# ig-normal-ver11.net
KiCad netlist of a schematic drawn in EAGLE
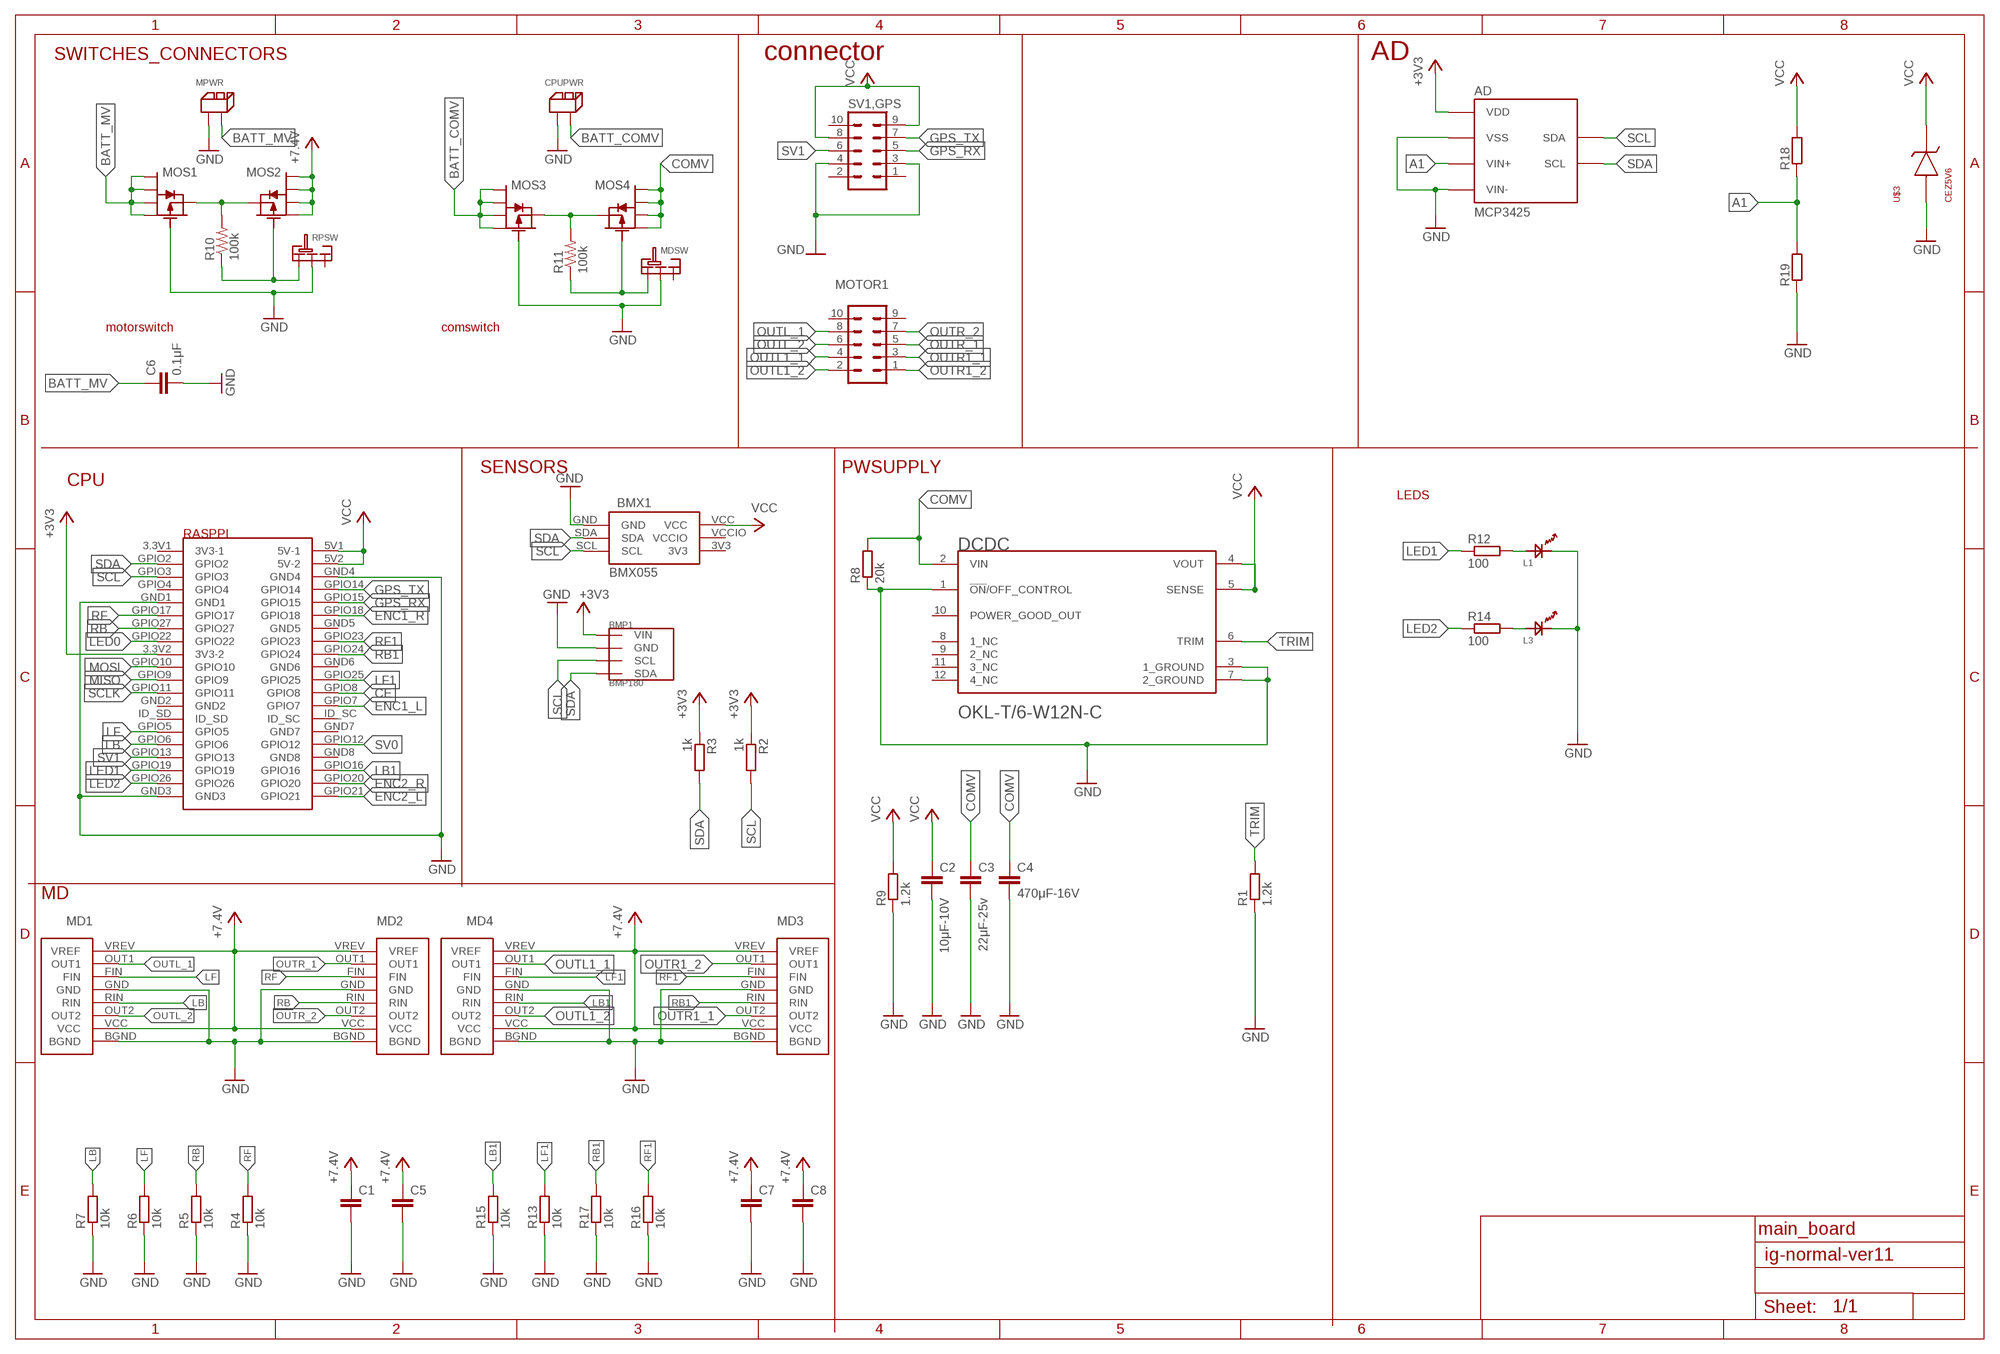
[diagram p0: schematic, sheet 1]

(export (version "E")
  (design (tool "Eeschema 10.0.6"))
  (components
    (comp (ref "AD")
      (value "MCP3425")
      (footprint "eagle-import:SOT23-6")
      (libsource (lib "eagle-import") (part "MCP3425"))
    )
    (comp (ref "BMP1")
      (value "BMP180")
      (footprint "eagle-import:GY-68")
      (libsource (lib "eagle-import") (part "BMP180"))
    )
    (comp (ref "BMX1")
      (value "BMX055")
      (footprint "eagle-import:BMX055")
      (libsource (lib "eagle-import") (part "BMX055"))
    )
    (comp (ref "C1")
      (value "C-EUC0603")
      (footprint "eagle-import:C0603")
      (libsource (lib "eagle-import") (part "C-EUC0603"))
    )
    (comp (ref "C2")
      (value "10μF-10V")
      (footprint "eagle-import:C0603")
      (libsource (lib "eagle-import") (part "C-EUC0603"))
    )
    (comp (ref "C3")
      (value "22μF-25v")
      (footprint "eagle-import:C0805")
      (libsource (lib "eagle-import") (part "C-EUC0805"))
    )
    (comp (ref "C4")
      (value "470μF-16V")
      (footprint "eagle-import:C0603")
      (libsource (lib "eagle-import") (part "C-EUC0603"))
    )
    (comp (ref "C5")
      (value "C-EUC0603")
      (footprint "eagle-import:C0603")
      (libsource (lib "eagle-import") (part "C-EUC0603"))
    )
    (comp (ref "C6")
      (value "0.1μF")
      (footprint "eagle-import:C0603")
      (libsource (lib "eagle-import") (part "C-EUC0603"))
    )
    (comp (ref "C7")
      (value "C-EUC0603")
      (footprint "eagle-import:C0603")
      (libsource (lib "eagle-import") (part "C-EUC0603"))
    )
    (comp (ref "C8")
      (value "C-EUC0603")
      (footprint "eagle-import:C0603")
      (libsource (lib "eagle-import") (part "C-EUC0603"))
    )
    (comp (ref "CPUPWR")
      (value "2PIN")
      (footprint "eagle-import:2PIN")
      (libsource (lib "eagle-import") (part "2PIN"))
    )
    (comp (ref "DCDC")
      (value "OKL-T/6-W12N-CMURATA_OKL-T-6-W12N-C_0_0")
      (footprint "eagle-import:MURATA_OKL-T-6-W12N-C_0")
      (fields
        (field (name "DIGIKEY_PART_NUMBER") "811-2214-1-ND")
        (field (name "MF") "Murata")
        (field (name "MOUSER_PART_NUMBER") "580-OKL-T/6-W12N-C")
      )
      (libsource (lib "eagle-import") (part "OKL-T/6-W12N-CMURATA_OKL-T-6-W12N-C_0_0"))
    )
    (comp (ref "L1")
      (value "OSXX1608C1A")
      (footprint "eagle-import:OSXX1608C1A")
      (libsource (lib "eagle-import") (part "OSXX1608C1A"))
    )
    (comp (ref "L3")
      (value "OSXX1608C1A")
      (footprint "eagle-import:OSXX1608C1A")
      (libsource (lib "eagle-import") (part "OSXX1608C1A"))
    )
    (comp (ref "MD1")
      (value "BD6222HFP-TR")
      (footprint "eagle-import:BD6222HFP-TR")
      (libsource (lib "eagle-import") (part "BD6222HFP-TR"))
    )
    (comp (ref "MD2")
      (value "BD6222HFP-TR")
      (footprint "eagle-import:BD6222HFP-TR")
      (libsource (lib "eagle-import") (part "BD6222HFP-TR"))
    )
    (comp (ref "MD3")
      (value "BD6222HFP-TR")
      (footprint "eagle-import:BD6222HFP-TR")
      (libsource (lib "eagle-import") (part "BD6222HFP-TR"))
    )
    (comp (ref "MD4")
      (value "BD6222HFP-TR")
      (footprint "eagle-import:BD6222HFP-TR")
      (libsource (lib "eagle-import") (part "BD6222HFP-TR"))
    )
    (comp (ref "MDSW")
      (value "SRIDE_SWITCH")
      (footprint "eagle-import:SRIDE_SWITCH")
      (libsource (lib "eagle-import") (part "SRIDE_SWITCH"))
    )
    (comp (ref "MOS1")
      (value "PCH_SSM6J808R")
      (footprint "eagle-import:SSM6J808R")
      (libsource (lib "eagle-import") (part "PCH_SSM6J808R"))
    )
    (comp (ref "MOS2")
      (value "PCH_SSM6J808R")
      (footprint "eagle-import:SSM6J808R")
      (libsource (lib "eagle-import") (part "PCH_SSM6J808R"))
    )
    (comp (ref "MOS3")
      (value "PCH_SSM6J808R")
      (footprint "eagle-import:SSM6J808R")
      (libsource (lib "eagle-import") (part "PCH_SSM6J808R"))
    )
    (comp (ref "MOS4")
      (value "PCH_SSM6J808R")
      (footprint "eagle-import:SSM6J808R")
      (libsource (lib "eagle-import") (part "PCH_SSM6J808R"))
    )
    (comp (ref "MOTOR1")
      (value "ML10L")
      (footprint "eagle-import:ML10L")
      (libsource (lib "eagle-import") (part "ML10L"))
    )
    (comp (ref "MPWR")
      (value "2PIN")
      (footprint "eagle-import:2PIN")
      (libsource (lib "eagle-import") (part "2PIN"))
    )
    (comp (ref "R1")
      (value "1.2k")
      (footprint "eagle-import:R0805")
      (libsource (lib "eagle-import") (part "R-EU_R0805"))
    )
    (comp (ref "R2")
      (value "1k")
      (footprint "eagle-import:R0603")
      (libsource (lib "eagle-import") (part "R-EU_R0603"))
    )
    (comp (ref "R3")
      (value "1k")
      (footprint "eagle-import:R0603")
      (libsource (lib "eagle-import") (part "R-EU_R0603"))
    )
    (comp (ref "R4")
      (value "10k")
      (footprint "eagle-import:R0603")
      (libsource (lib "eagle-import") (part "R-EU_R0603"))
    )
    (comp (ref "R5")
      (value "10k")
      (footprint "eagle-import:R0603")
      (libsource (lib "eagle-import") (part "R-EU_R0603"))
    )
    (comp (ref "R6")
      (value "10k")
      (footprint "eagle-import:R0603")
      (libsource (lib "eagle-import") (part "R-EU_R0603"))
    )
    (comp (ref "R7")
      (value "10k")
      (footprint "eagle-import:R0603")
      (libsource (lib "eagle-import") (part "R-EU_R0603"))
    )
    (comp (ref "R8")
      (value "20k")
      (footprint "eagle-import:R0603")
      (libsource (lib "eagle-import") (part "R-EU_R0603"))
    )
    (comp (ref "R9")
      (value "1.2k")
      (footprint "eagle-import:R0805")
      (libsource (lib "eagle-import") (part "R-EU_R0805"))
    )
    (comp (ref "R10")
      (value "100k")
      (footprint "eagle-import:R0603")
      (libsource (lib "eagle-import") (part "R-US_R0603"))
    )
    (comp (ref "R11")
      (value "100k")
      (footprint "eagle-import:R0603")
      (libsource (lib "eagle-import") (part "R-US_R0603"))
    )
    (comp (ref "R12")
      (value "100")
      (footprint "eagle-import:R0603")
      (libsource (lib "eagle-import") (part "R-EU_R0603"))
    )
    (comp (ref "R13")
      (value "10k")
      (footprint "eagle-import:R0603")
      (libsource (lib "eagle-import") (part "R-EU_R0603"))
    )
    (comp (ref "R14")
      (value "100")
      (footprint "eagle-import:R0603")
      (libsource (lib "eagle-import") (part "R-EU_R0603"))
    )
    (comp (ref "R15")
      (value "10k")
      (footprint "eagle-import:R0603")
      (libsource (lib "eagle-import") (part "R-EU_R0603"))
    )
    (comp (ref "R16")
      (value "10k")
      (footprint "eagle-import:R0603")
      (libsource (lib "eagle-import") (part "R-EU_R0603"))
    )
    (comp (ref "R17")
      (value "10k")
      (footprint "eagle-import:R0603")
      (libsource (lib "eagle-import") (part "R-EU_R0603"))
    )
    (comp (ref "R18")
      (value "R-EU_R0603")
      (footprint "eagle-import:R0603")
      (libsource (lib "eagle-import") (part "R-EU_R0603"))
    )
    (comp (ref "R19")
      (value "R-EU_R0603")
      (footprint "eagle-import:R0603")
      (libsource (lib "eagle-import") (part "R-EU_R0603"))
    )
    (comp (ref "RASPPI")
      (value "RASPBERYPIZEROW")
      (footprint "eagle-import:RASPBERYPIZEROW")
      (libsource (lib "eagle-import") (part "RASPBERYPIZEROW"))
    )
    (comp (ref "RPSW")
      (value "SRIDE_SWITCH")
      (footprint "eagle-import:SRIDE_SWITCH")
      (libsource (lib "eagle-import") (part "SRIDE_SWITCH"))
    )
    (comp (ref "SV1,GPS")
      (value "ML10L")
      (footprint "eagle-import:ML10L")
      (libsource (lib "eagle-import") (part "ML10L"))
    )
    (comp (ref "U$3")
      (value "CEZ5V6")
      (footprint "eagle-import:CEZ5V6")
      (libsource (lib "eagle-import") (part "CEZ5V6"))
    )
  )
  (nets
    (net (code "1") (name "+3V3") (class "Default")
      (node (ref "AD") (pin "5") (pinfunction "VDD_5") (pintype "power_in"))
      (node (ref "BMP1") (pin "P1") (pinfunction "VIN_P1") (pintype "bidirectional"))
      (node (ref "R2") (pin "1") (pinfunction "1_1") (pintype "passive"))
      (node (ref "R3") (pin "1") (pinfunction "1_1") (pintype "passive"))
      (node (ref "RASPPI") (pin "3.3V2") (pinfunction "3V3-2_3.3V2") (pintype "bidirectional"))
    )
    (net (code "2") (name "+7.4V") (class "Default")
      (node (ref "C1") (pin "1") (pinfunction "1_1") (pintype "passive"))
      (node (ref "C5") (pin "1") (pinfunction "1_1") (pintype "passive"))
      (node (ref "C7") (pin "1") (pinfunction "1_1") (pintype "passive"))
      (node (ref "C8") (pin "1") (pinfunction "1_1") (pintype "passive"))
      (node (ref "MD1") (pin "VCC") (pinfunction "VCC_VCC") (pintype "bidirectional"))
      (node (ref "MD1") (pin "VREV") (pinfunction "VREF_VREV") (pintype "bidirectional"))
      (node (ref "MD2") (pin "VCC") (pinfunction "VCC_VCC") (pintype "bidirectional"))
      (node (ref "MD2") (pin "VREV") (pinfunction "VREF_VREV") (pintype "bidirectional"))
      (node (ref "MD3") (pin "VCC") (pinfunction "VCC_VCC") (pintype "bidirectional"))
      (node (ref "MD3") (pin "VREV") (pinfunction "VREF_VREV") (pintype "bidirectional"))
      (node (ref "MD4") (pin "VCC") (pinfunction "VCC_VCC") (pintype "bidirectional"))
      (node (ref "MD4") (pin "VREV") (pinfunction "VREF_VREV") (pintype "bidirectional"))
      (node (ref "MOS2") (pin "1") (pinfunction "1_1") (pintype "bidirectional"))
      (node (ref "MOS2") (pin "2") (pinfunction "2_2") (pintype "bidirectional"))
      (node (ref "MOS2") (pin "5") (pinfunction "5_5") (pintype "bidirectional"))
      (node (ref "MOS2") (pin "6") (pinfunction "6_6") (pintype "bidirectional"))
    )
    (net (code "3") (name "/3V3") (class "Default")
      (node (ref "BMX1") (pin "3V3") (pinfunction "3V3_3V3") (pintype "power_in"))
    )
    (net (code "4") (name "/VCCIO") (class "Default")
      (node (ref "BMX1") (pin "VCCIO") (pinfunction "VCCIO_VCCIO") (pintype "power_in"))
    )
    (net (code "5") (name "A1") (class "Default")
      (node (ref "AD") (pin "1") (pinfunction "VIN+_1") (pintype "input"))
      (node (ref "R18") (pin "1") (pinfunction "1_1") (pintype "passive"))
      (node (ref "R19") (pin "2") (pinfunction "2_2") (pintype "passive"))
    )
    (net (code "6") (name "BATT_COMV") (class "Default")
      (node (ref "CPUPWR") (pin "P$2") (pinfunction "P$2_P$2") (pintype "bidirectional"))
      (node (ref "MOS3") (pin "1") (pinfunction "1_1") (pintype "bidirectional"))
      (node (ref "MOS3") (pin "2") (pinfunction "2_2") (pintype "bidirectional"))
      (node (ref "MOS3") (pin "5") (pinfunction "5_5") (pintype "bidirectional"))
      (node (ref "MOS3") (pin "6") (pinfunction "6_6") (pintype "bidirectional"))
    )
    (net (code "7") (name "BATT_MV") (class "Default")
      (node (ref "C6") (pin "1") (pinfunction "1_1") (pintype "passive"))
      (node (ref "MOS1") (pin "1") (pinfunction "1_1") (pintype "bidirectional"))
      (node (ref "MOS1") (pin "2") (pinfunction "2_2") (pintype "bidirectional"))
      (node (ref "MOS1") (pin "5") (pinfunction "5_5") (pintype "bidirectional"))
      (node (ref "MOS1") (pin "6") (pinfunction "6_6") (pintype "bidirectional"))
      (node (ref "MPWR") (pin "P$2") (pinfunction "P$2_P$2") (pintype "bidirectional"))
    )
    (net (code "8") (name "CE") (class "Default")
      (node (ref "RASPPI") (pin "GPIO8") (pinfunction "GPIO8_GPIO8") (pintype "bidirectional"))
    )
    (net (code "9") (name "COMV") (class "Default")
      (node (ref "C3") (pin "1") (pinfunction "1_1") (pintype "passive"))
      (node (ref "C4") (pin "1") (pinfunction "1_1") (pintype "passive"))
      (node (ref "DCDC") (pin "2") (pinfunction "VIN_2") (pintype "bidirectional"))
      (node (ref "MOS4") (pin "1") (pinfunction "1_1") (pintype "bidirectional"))
      (node (ref "MOS4") (pin "2") (pinfunction "2_2") (pintype "bidirectional"))
      (node (ref "MOS4") (pin "5") (pinfunction "5_5") (pintype "bidirectional"))
      (node (ref "MOS4") (pin "6") (pinfunction "6_6") (pintype "bidirectional"))
      (node (ref "R8") (pin "2") (pinfunction "2_2") (pintype "passive"))
    )
    (net (code "10") (name "ENC1_L") (class "Default")
      (node (ref "RASPPI") (pin "GPIO7") (pinfunction "GPIO7_GPIO7") (pintype "bidirectional"))
    )
    (net (code "11") (name "ENC1_R") (class "Default")
      (node (ref "RASPPI") (pin "GPIO18") (pinfunction "GPIO18_GPIO18") (pintype "bidirectional"))
    )
    (net (code "12") (name "ENC2_L") (class "Default")
      (node (ref "RASPPI") (pin "GPIO21") (pinfunction "GPIO21_GPIO21") (pintype "bidirectional"))
    )
    (net (code "13") (name "ENC2_R") (class "Default")
      (node (ref "RASPPI") (pin "GPIO20") (pinfunction "GPIO20_GPIO20") (pintype "bidirectional"))
    )
    (net (code "14") (name "GND") (class "Default")
      (node (ref "AD") (pin "2") (pinfunction "VSS_2") (pintype "power_in"))
      (node (ref "AD") (pin "6") (pinfunction "VIN-_6") (pintype "input"))
      (node (ref "BMP1") (pin "P2") (pinfunction "GND_P2") (pintype "bidirectional"))
      (node (ref "BMX1") (pin "GND") (pinfunction "GND_GND") (pintype "power_in"))
      (node (ref "C1") (pin "2") (pinfunction "2_2") (pintype "passive"))
      (node (ref "C2") (pin "2") (pinfunction "2_2") (pintype "passive"))
      (node (ref "C3") (pin "2") (pinfunction "2_2") (pintype "passive"))
      (node (ref "C4") (pin "2") (pinfunction "2_2") (pintype "passive"))
      (node (ref "C5") (pin "2") (pinfunction "2_2") (pintype "passive"))
      (node (ref "C6") (pin "2") (pinfunction "2_2") (pintype "passive"))
      (node (ref "C7") (pin "2") (pinfunction "2_2") (pintype "passive"))
      (node (ref "C8") (pin "2") (pinfunction "2_2") (pintype "passive"))
      (node (ref "CPUPWR") (pin "P$1") (pinfunction "P$1_P$1") (pintype "bidirectional"))
      (node (ref "DCDC") (pin "1") (pinfunction "~{ON}/OFF_CONTROL_1") (pintype "bidirectional"))
      (node (ref "DCDC") (pin "3") (pinfunction "1_GROUND_3") (pintype "power_in"))
      (node (ref "DCDC") (pin "7") (pinfunction "2_GROUND_7") (pintype "power_in"))
      (node (ref "L1") (pin "CT") (pinfunction "CT_CT") (pintype "bidirectional"))
      (node (ref "L3") (pin "CT") (pinfunction "CT_CT") (pintype "bidirectional"))
      (node (ref "MD1") (pin "BGND") (pinfunction "BGND_BGND") (pintype "bidirectional"))
      (node (ref "MD1") (pin "GND") (pinfunction "GND_GND") (pintype "bidirectional"))
      (node (ref "MD2") (pin "BGND") (pinfunction "BGND_BGND") (pintype "bidirectional"))
      (node (ref "MD2") (pin "GND") (pinfunction "GND_GND") (pintype "bidirectional"))
      (node (ref "MD3") (pin "BGND") (pinfunction "BGND_BGND") (pintype "bidirectional"))
      (node (ref "MD3") (pin "GND") (pinfunction "GND_GND") (pintype "bidirectional"))
      (node (ref "MD4") (pin "BGND") (pinfunction "BGND_BGND") (pintype "bidirectional"))
      (node (ref "MD4") (pin "GND") (pinfunction "GND_GND") (pintype "bidirectional"))
      (node (ref "MDSW") (pin "LR") (pinfunction "LR_LR") (pintype "bidirectional"))
      (node (ref "MOS1") (pin "3") (pinfunction "3_3") (pintype "bidirectional"))
      (node (ref "MOS3") (pin "3") (pinfunction "3_3") (pintype "bidirectional"))
      (node (ref "MPWR") (pin "P$1") (pinfunction "P$1_P$1") (pintype "bidirectional"))
      (node (ref "R1") (pin "1") (pinfunction "1_1") (pintype "passive"))
      (node (ref "R13") (pin "1") (pinfunction "1_1") (pintype "passive"))
      (node (ref "R15") (pin "1") (pinfunction "1_1") (pintype "passive"))
      (node (ref "R16") (pin "1") (pinfunction "1_1") (pintype "passive"))
      (node (ref "R17") (pin "1") (pinfunction "1_1") (pintype "passive"))
      (node (ref "R19") (pin "1") (pinfunction "1_1") (pintype "passive"))
      (node (ref "R4") (pin "1") (pinfunction "1_1") (pintype "passive"))
      (node (ref "R5") (pin "1") (pinfunction "1_1") (pintype "passive"))
      (node (ref "R6") (pin "1") (pinfunction "1_1") (pintype "passive"))
      (node (ref "R7") (pin "1") (pinfunction "1_1") (pintype "passive"))
      (node (ref "R8") (pin "1") (pinfunction "1_1") (pintype "passive"))
      (node (ref "R9") (pin "1") (pinfunction "1_1") (pintype "passive"))
      (node (ref "RASPPI") (pin "GND1") (pinfunction "GND1_GND1") (pintype "bidirectional"))
      (node (ref "RASPPI") (pin "GND3") (pinfunction "GND3_GND3") (pintype "bidirectional"))
      (node (ref "RASPPI") (pin "GND4") (pinfunction "GND4_GND4") (pintype "bidirectional"))
      (node (ref "RPSW") (pin "LR") (pinfunction "LR_LR") (pintype "bidirectional"))
      (node (ref "SV1,GPS") (pin "3") (pinfunction "3_3") (pintype "passive"))
      (node (ref "SV1,GPS") (pin "4") (pinfunction "4_4") (pintype "passive"))
      (node (ref "U$3") (pin "P$1") (pinfunction "P$1_P$1") (pintype "bidirectional"))
    )
    (net (code "15") (name "GPS_RX") (class "Default")
      (node (ref "RASPPI") (pin "GPIO15") (pinfunction "GPIO15_GPIO15") (pintype "bidirectional"))
      (node (ref "SV1,GPS") (pin "5") (pinfunction "5_5") (pintype "passive"))
    )
    (net (code "16") (name "GPS_TX") (class "Default")
      (node (ref "RASPPI") (pin "GPIO14") (pinfunction "GPIO14_GPIO14") (pintype "bidirectional"))
      (node (ref "SV1,GPS") (pin "7") (pinfunction "7_7") (pintype "passive"))
    )
    (net (code "17") (name "LB") (class "Default")
      (node (ref "MD1") (pin "RIN") (pinfunction "RIN_RIN") (pintype "bidirectional"))
      (node (ref "R7") (pin "2") (pinfunction "2_2") (pintype "passive"))
      (node (ref "RASPPI") (pin "GPIO6") (pinfunction "GPIO6_GPIO6") (pintype "bidirectional"))
    )
    (net (code "18") (name "LB1") (class "Default")
      (node (ref "MD4") (pin "RIN") (pinfunction "RIN_RIN") (pintype "bidirectional"))
      (node (ref "R15") (pin "2") (pinfunction "2_2") (pintype "passive"))
      (node (ref "RASPPI") (pin "GPIO16") (pinfunction "GPIO16_GPIO16") (pintype "bidirectional"))
    )
    (net (code "19") (name "LED0") (class "Default")
      (node (ref "RASPPI") (pin "GPIO22") (pinfunction "GPIO22_GPIO22") (pintype "bidirectional"))
    )
    (net (code "20") (name "LED1") (class "Default")
      (node (ref "R12") (pin "1") (pinfunction "1_1") (pintype "passive"))
      (node (ref "RASPPI") (pin "GPIO19") (pinfunction "GPIO19_GPIO19") (pintype "bidirectional"))
    )
    (net (code "21") (name "LED2") (class "Default")
      (node (ref "R14") (pin "1") (pinfunction "1_1") (pintype "passive"))
      (node (ref "RASPPI") (pin "GPIO26") (pinfunction "GPIO26_GPIO26") (pintype "bidirectional"))
    )
    (net (code "22") (name "LF") (class "Default")
      (node (ref "MD1") (pin "FIN") (pinfunction "FIN_FIN") (pintype "bidirectional"))
      (node (ref "R6") (pin "2") (pinfunction "2_2") (pintype "passive"))
      (node (ref "RASPPI") (pin "GPIO5") (pinfunction "GPIO5_GPIO5") (pintype "bidirectional"))
    )
    (net (code "23") (name "LF1") (class "Default")
      (node (ref "MD4") (pin "FIN") (pinfunction "FIN_FIN") (pintype "bidirectional"))
      (node (ref "R13") (pin "2") (pinfunction "2_2") (pintype "passive"))
      (node (ref "RASPPI") (pin "GPIO25") (pinfunction "GPIO25_GPIO25") (pintype "bidirectional"))
    )
    (net (code "24") (name "MISO") (class "Default")
      (node (ref "RASPPI") (pin "GPIO9") (pinfunction "GPIO9_GPIO9") (pintype "bidirectional"))
    )
    (net (code "25") (name "MOSI") (class "Default")
      (node (ref "RASPPI") (pin "GPIO10") (pinfunction "GPIO10_GPIO10") (pintype "bidirectional"))
    )
    (net (code "26") (name "Net-(L1-PadAN)") (class "Default")
      (node (ref "L1") (pin "AN") (pinfunction "AN_AN") (pintype "bidirectional"))
      (node (ref "R12") (pin "2") (pinfunction "2_2") (pintype "passive"))
    )
    (net (code "27") (name "Net-(L3-PadAN)") (class "Default")
      (node (ref "L3") (pin "AN") (pinfunction "AN_AN") (pintype "bidirectional"))
      (node (ref "R14") (pin "2") (pinfunction "2_2") (pintype "passive"))
    )
    (net (code "28") (name "Net-(MDSW-PadL)") (class "Default")
      (node (ref "MDSW") (pin "L") (pinfunction "L_L") (pintype "bidirectional"))
      (node (ref "MOS4") (pin "3") (pinfunction "3_3") (pintype "bidirectional"))
      (node (ref "R11") (pin "1") (pinfunction "1_1") (pintype "passive"))
    )
    (net (code "29") (name "Net-(MOS1-Pad4)") (class "Default")
      (node (ref "MOS1") (pin "4") (pinfunction "4_4") (pintype "bidirectional"))
      (node (ref "MOS2") (pin "4") (pinfunction "4_4") (pintype "bidirectional"))
      (node (ref "R10") (pin "2") (pinfunction "2_2") (pintype "passive"))
    )
    (net (code "30") (name "Net-(MOS2-Pad3)") (class "Default")
      (node (ref "MOS2") (pin "3") (pinfunction "3_3") (pintype "bidirectional"))
      (node (ref "R10") (pin "1") (pinfunction "1_1") (pintype "passive"))
      (node (ref "RPSW") (pin "L") (pinfunction "L_L") (pintype "bidirectional"))
    )
    (net (code "31") (name "Net-(MOS3-Pad4)") (class "Default")
      (node (ref "MOS3") (pin "4") (pinfunction "4_4") (pintype "bidirectional"))
      (node (ref "MOS4") (pin "4") (pinfunction "4_4") (pintype "bidirectional"))
      (node (ref "R11") (pin "2") (pinfunction "2_2") (pintype "passive"))
    )
    (net (code "32") (name "OUTL1_1") (class "Default")
      (node (ref "MD4") (pin "OUT1") (pinfunction "OUT1_OUT1") (pintype "bidirectional"))
      (node (ref "MOTOR1") (pin "4") (pinfunction "4_4") (pintype "passive"))
    )
    (net (code "33") (name "OUTL1_2") (class "Default")
      (node (ref "MD4") (pin "OUT2") (pinfunction "OUT2_OUT2") (pintype "bidirectional"))
      (node (ref "MOTOR1") (pin "2") (pinfunction "2_2") (pintype "passive"))
    )
    (net (code "34") (name "OUTL_1") (class "Default")
      (node (ref "MD1") (pin "OUT1") (pinfunction "OUT1_OUT1") (pintype "bidirectional"))
      (node (ref "MOTOR1") (pin "8") (pinfunction "8_8") (pintype "passive"))
    )
    (net (code "35") (name "OUTL_2") (class "Default")
      (node (ref "MD1") (pin "OUT2") (pinfunction "OUT2_OUT2") (pintype "bidirectional"))
      (node (ref "MOTOR1") (pin "6") (pinfunction "6_6") (pintype "passive"))
    )
    (net (code "36") (name "OUTR1_1") (class "Default")
      (node (ref "MD3") (pin "OUT2") (pinfunction "OUT2_OUT2") (pintype "bidirectional"))
      (node (ref "MOTOR1") (pin "3") (pinfunction "3_3") (pintype "passive"))
    )
    (net (code "37") (name "OUTR1_2") (class "Default")
      (node (ref "MD3") (pin "OUT1") (pinfunction "OUT1_OUT1") (pintype "bidirectional"))
      (node (ref "MOTOR1") (pin "1") (pinfunction "1_1") (pintype "passive"))
    )
    (net (code "38") (name "OUTR_1") (class "Default")
      (node (ref "MD2") (pin "OUT1") (pinfunction "OUT1_OUT1") (pintype "bidirectional"))
      (node (ref "MOTOR1") (pin "5") (pinfunction "5_5") (pintype "passive"))
    )
    (net (code "39") (name "OUTR_2") (class "Default")
      (node (ref "MD2") (pin "OUT2") (pinfunction "OUT2_OUT2") (pintype "bidirectional"))
      (node (ref "MOTOR1") (pin "7") (pinfunction "7_7") (pintype "passive"))
    )
    (net (code "40") (name "RB") (class "Default")
      (node (ref "MD2") (pin "RIN") (pinfunction "RIN_RIN") (pintype "bidirectional"))
      (node (ref "R5") (pin "2") (pinfunction "2_2") (pintype "passive"))
      (node (ref "RASPPI") (pin "GPIO27") (pinfunction "GPIO27_GPIO27") (pintype "bidirectional"))
    )
    (net (code "41") (name "RB1") (class "Default")
      (node (ref "MD3") (pin "RIN") (pinfunction "RIN_RIN") (pintype "bidirectional"))
      (node (ref "R17") (pin "2") (pinfunction "2_2") (pintype "passive"))
      (node (ref "RASPPI") (pin "GPIO24") (pinfunction "GPIO24_GPIO24") (pintype "bidirectional"))
    )
    (net (code "42") (name "RF") (class "Default")
      (node (ref "MD2") (pin "FIN") (pinfunction "FIN_FIN") (pintype "bidirectional"))
      (node (ref "R4") (pin "2") (pinfunction "2_2") (pintype "passive"))
      (node (ref "RASPPI") (pin "GPIO17") (pinfunction "GPIO17_GPIO17") (pintype "bidirectional"))
    )
    (net (code "43") (name "RF1") (class "Default")
      (node (ref "MD3") (pin "FIN") (pinfunction "FIN_FIN") (pintype "bidirectional"))
      (node (ref "R16") (pin "2") (pinfunction "2_2") (pintype "passive"))
      (node (ref "RASPPI") (pin "GPIO23") (pinfunction "GPIO23_GPIO23") (pintype "bidirectional"))
    )
    (net (code "44") (name "SCL") (class "Default")
      (node (ref "AD") (pin "4") (pinfunction "SDA_4") (pintype "bidirectional"))
      (node (ref "BMP1") (pin "P3") (pinfunction "SCL_P3") (pintype "bidirectional"))
      (node (ref "BMX1") (pin "SCL") (pinfunction "SCL_SCL") (pintype "bidirectional"))
      (node (ref "R2") (pin "2") (pinfunction "2_2") (pintype "passive"))
      (node (ref "RASPPI") (pin "GPIO3") (pinfunction "GPIO3_GPIO3") (pintype "bidirectional"))
    )
    (net (code "45") (name "SCLK") (class "Default")
      (node (ref "RASPPI") (pin "GPIO11") (pinfunction "GPIO11_GPIO11") (pintype "bidirectional"))
    )
    (net (code "46") (name "SDA") (class "Default")
      (node (ref "AD") (pin "3") (pinfunction "SCL_3") (pintype "bidirectional"))
      (node (ref "BMP1") (pin "P4") (pinfunction "SDA_P4") (pintype "bidirectional"))
      (node (ref "BMX1") (pin "SDA") (pinfunction "SDA_SDA") (pintype "bidirectional"))
      (node (ref "R3") (pin "2") (pinfunction "2_2") (pintype "passive"))
      (node (ref "RASPPI") (pin "GPIO2") (pinfunction "GPIO2_GPIO2") (pintype "bidirectional"))
    )
    (net (code "47") (name "SV0") (class "Default")
      (node (ref "RASPPI") (pin "GPIO12") (pinfunction "GPIO12_GPIO12") (pintype "bidirectional"))
    )
    (net (code "48") (name "SV1") (class "Default")
      (node (ref "RASPPI") (pin "GPIO13") (pinfunction "GPIO13_GPIO13") (pintype "bidirectional"))
      (node (ref "SV1,GPS") (pin "6") (pinfunction "6_6") (pintype "passive"))
    )
    (net (code "49") (name "TRIM") (class "Default")
      (node (ref "DCDC") (pin "6") (pinfunction "TRIM_6") (pintype "passive"))
      (node (ref "R1") (pin "2") (pinfunction "2_2") (pintype "passive"))
    )
    (net (code "50") (name "VCC") (class "Default")
      (node (ref "BMX1") (pin "VCC") (pinfunction "VCC_VCC") (pintype "power_in"))
      (node (ref "C2") (pin "1") (pinfunction "1_1") (pintype "passive"))
      (node (ref "DCDC") (pin "4") (pinfunction "VOUT_4") (pintype "bidirectional"))
      (node (ref "DCDC") (pin "5") (pinfunction "SENSE_5") (pintype "passive"))
      (node (ref "R18") (pin "2") (pinfunction "2_2") (pintype "passive"))
      (node (ref "R9") (pin "2") (pinfunction "2_2") (pintype "passive"))
      (node (ref "RASPPI") (pin "5V1") (pinfunction "5V-1_5V1") (pintype "bidirectional"))
      (node (ref "RASPPI") (pin "5V2") (pinfunction "5V-2_5V2") (pintype "bidirectional"))
      (node (ref "SV1,GPS") (pin "8") (pinfunction "8_8") (pintype "passive"))
      (node (ref "SV1,GPS") (pin "9") (pinfunction "9_9") (pintype "passive"))
      (node (ref "U$3") (pin "P$2") (pinfunction "P$2_P$2") (pintype "bidirectional"))
    )
    (net (code "51") (name "unconnected-(DCDC-1_NC-Pad8)") (class "Default")
      (node (ref "DCDC") (pin "8") (pinfunction "1_NC_8") (pintype "passive"))
    )
    (net (code "52") (name "unconnected-(DCDC-2_NC-Pad9)") (class "Default")
      (node (ref "DCDC") (pin "9") (pinfunction "2_NC_9") (pintype "passive"))
    )
    (net (code "53") (name "unconnected-(DCDC-3_NC-Pad11)") (class "Default")
      (node (ref "DCDC") (pin "11") (pinfunction "3_NC_11") (pintype "passive"))
    )
    (net (code "54") (name "unconnected-(DCDC-4_NC-Pad12)") (class "Default")
      (node (ref "DCDC") (pin "12") (pinfunction "4_NC_12") (pintype "passive"))
    )
    (net (code "55") (name "unconnected-(DCDC-POWER_GOOD_OUT-Pad10)") (class "Default")
      (node (ref "DCDC") (pin "10") (pinfunction "POWER_GOOD_OUT_10") (pintype "open_collector"))
    )
    (net (code "56") (name "unconnected-(MDSW-PadR)") (class "Default")
      (node (ref "MDSW") (pin "R") (pinfunction "R_R") (pintype "bidirectional"))
    )
    (net (code "57") (name "unconnected-(MOTOR1-Pad9)") (class "Default")
      (node (ref "MOTOR1") (pin "9") (pinfunction "9_9") (pintype "passive"))
    )
    (net (code "58") (name "unconnected-(MOTOR1-Pad10)") (class "Default")
      (node (ref "MOTOR1") (pin "10") (pinfunction "10_10") (pintype "passive"))
    )
    (net (code "59") (name "unconnected-(RASPPI-3V3-1-Pad3.3V1)") (class "Default")
      (node (ref "RASPPI") (pin "3.3V1") (pinfunction "3V3-1_3.3V1") (pintype "bidirectional"))
    )
    (net (code "60") (name "unconnected-(RASPPI-PadGND2)") (class "Default")
      (node (ref "RASPPI") (pin "GND2") (pinfunction "GND2_GND2") (pintype "bidirectional"))
    )
    (net (code "61") (name "unconnected-(RASPPI-PadGND5)") (class "Default")
      (node (ref "RASPPI") (pin "GND5") (pinfunction "GND5_GND5") (pintype "bidirectional"))
    )
    (net (code "62") (name "unconnected-(RASPPI-PadGND6)") (class "Default")
      (node (ref "RASPPI") (pin "GND6") (pinfunction "GND6_GND6") (pintype "bidirectional"))
    )
    (net (code "63") (name "unconnected-(RASPPI-PadGND7)") (class "Default")
      (node (ref "RASPPI") (pin "GND7") (pinfunction "GND7_GND7") (pintype "bidirectional"))
    )
    (net (code "64") (name "unconnected-(RASPPI-PadGND8)") (class "Default")
      (node (ref "RASPPI") (pin "GND8") (pinfunction "GND8_GND8") (pintype "bidirectional"))
    )
    (net (code "65") (name "unconnected-(RASPPI-PadGPIO4)") (class "Default")
      (node (ref "RASPPI") (pin "GPIO4") (pinfunction "GPIO4_GPIO4") (pintype "bidirectional"))
    )
    (net (code "66") (name "unconnected-(RASPPI-PadID_SC)") (class "Default")
      (node (ref "RASPPI") (pin "ID_SC") (pinfunction "ID_SC_ID_SC") (pintype "bidirectional"))
    )
    (net (code "67") (name "unconnected-(RASPPI-PadID_SD)") (class "Default")
      (node (ref "RASPPI") (pin "ID_SD") (pinfunction "ID_SD_ID_SD") (pintype "bidirectional"))
    )
    (net (code "68") (name "unconnected-(RPSW-PadR)") (class "Default")
      (node (ref "RPSW") (pin "R") (pinfunction "R_R") (pintype "bidirectional"))
    )
    (net (code "69") (name "unconnected-(SV1,GPS-Pad1)") (class "Default")
      (node (ref "SV1,GPS") (pin "1") (pinfunction "1_1") (pintype "passive"))
    )
    (net (code "70") (name "unconnected-(SV1,GPS-Pad2)") (class "Default")
      (node (ref "SV1,GPS") (pin "2") (pinfunction "2_2") (pintype "passive"))
    )
    (net (code "71") (name "unconnected-(SV1,GPS-Pad10)") (class "Default")
      (node (ref "SV1,GPS") (pin "10") (pinfunction "10_10") (pintype "passive"))
    )
  )
)
